# ArduinoInterface_v2.net
KiCad netlist of a schematic drawn in EAGLE
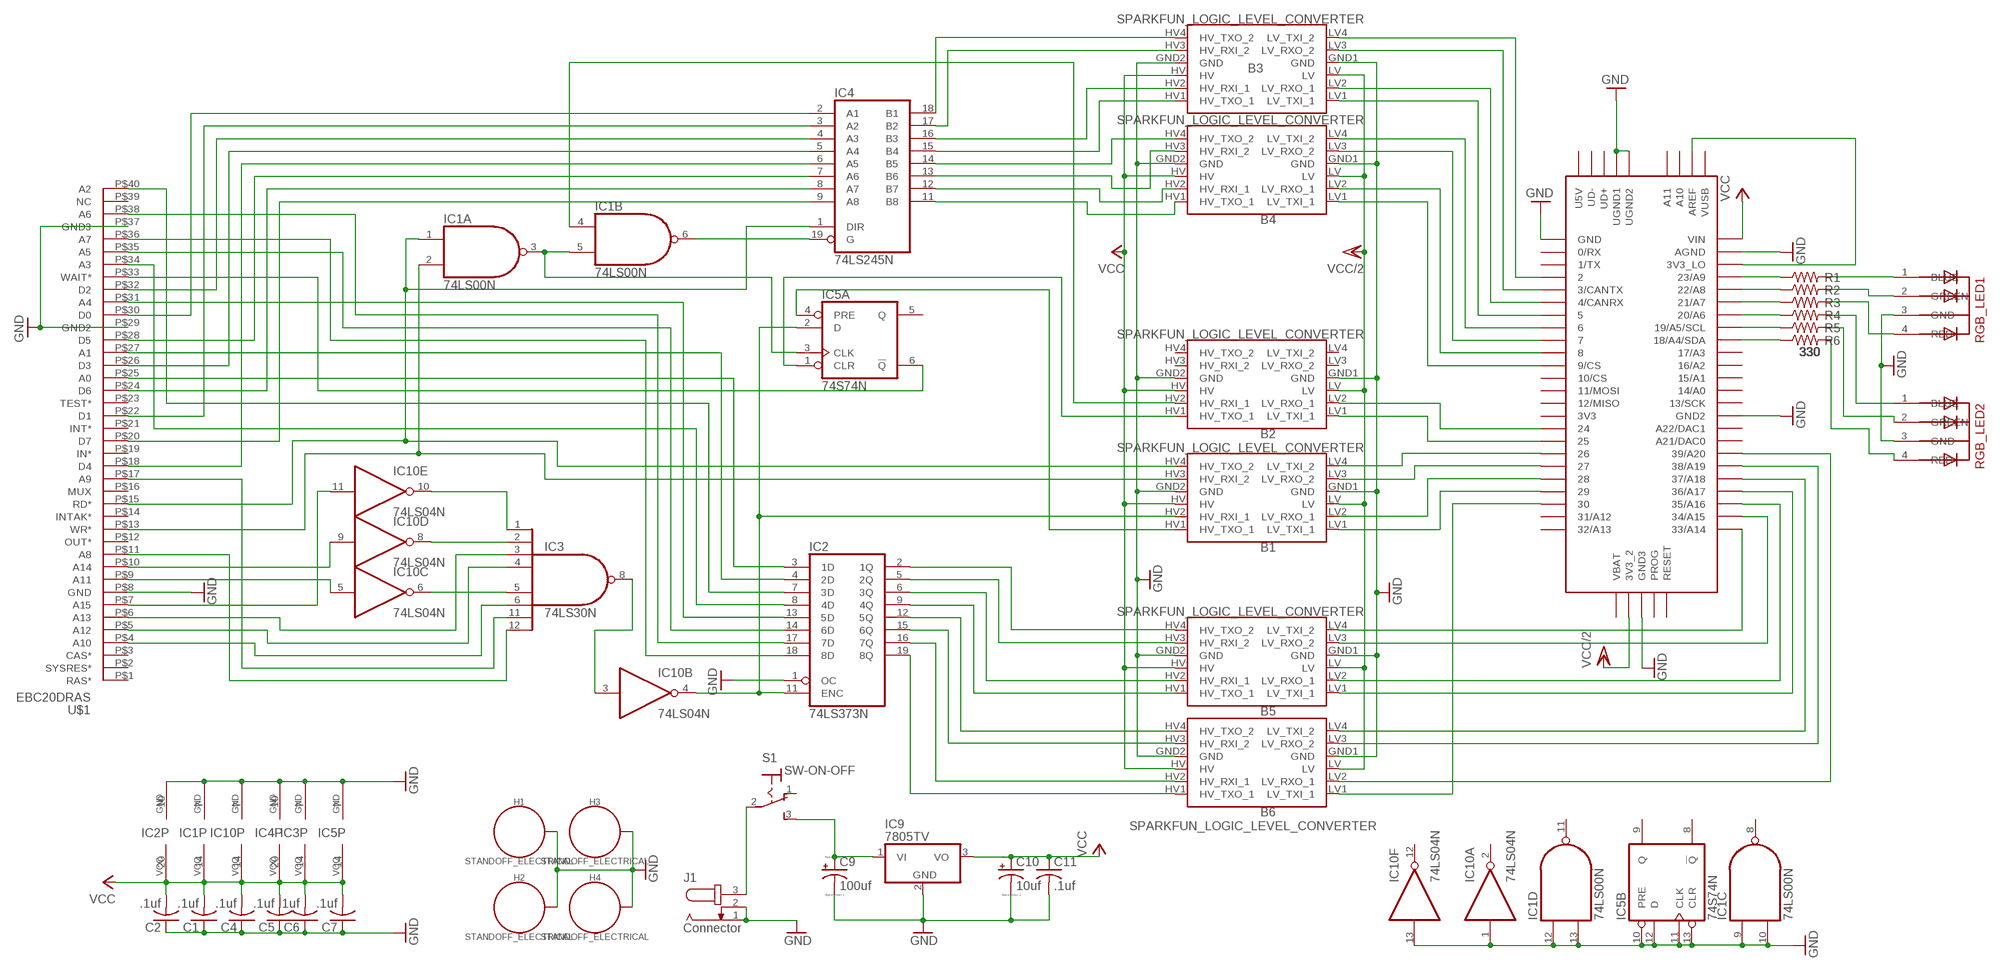
[diagram p0: schematic, sheet 1]

(export (version "E")
  (design (tool "Eeschema 10.0.6"))
  (components
    (comp (ref "B1")
      (value "SPARKFUN_LOGIC_LEVEL_CONVERTER")
      (footprint "eagle-import:SPARKFUN_LOGIC_LEVEL_CONVERTER")
      (libsource (lib "eagle-import") (part "SPARKFUN_LOGIC_LEVEL_CONVERTER"))
    )
    (comp (ref "B2")
      (value "SPARKFUN_LOGIC_LEVEL_CONVERTER")
      (footprint "eagle-import:SPARKFUN_LOGIC_LEVEL_CONVERTER")
      (libsource (lib "eagle-import") (part "SPARKFUN_LOGIC_LEVEL_CONVERTER"))
    )
    (comp (ref "B3")
      (value "SPARKFUN_LOGIC_LEVEL_CONVERTER")
      (footprint "eagle-import:SPARKFUN_LOGIC_LEVEL_CONVERTER")
      (libsource (lib "eagle-import") (part "SPARKFUN_LOGIC_LEVEL_CONVERTER"))
    )
    (comp (ref "B4")
      (value "SPARKFUN_LOGIC_LEVEL_CONVERTER")
      (footprint "eagle-import:SPARKFUN_LOGIC_LEVEL_CONVERTER")
      (libsource (lib "eagle-import") (part "SPARKFUN_LOGIC_LEVEL_CONVERTER"))
    )
    (comp (ref "B5")
      (value "SPARKFUN_LOGIC_LEVEL_CONVERTER")
      (footprint "eagle-import:SPARKFUN_LOGIC_LEVEL_CONVERTER")
      (libsource (lib "eagle-import") (part "SPARKFUN_LOGIC_LEVEL_CONVERTER"))
    )
    (comp (ref "B6")
      (value "SPARKFUN_LOGIC_LEVEL_CONVERTER")
      (footprint "eagle-import:SPARKFUN_LOGIC_LEVEL_CONVERTER")
      (libsource (lib "eagle-import") (part "SPARKFUN_LOGIC_LEVEL_CONVERTER"))
    )
    (comp (ref "C1")
      (value ".1uf")
      (footprint "eagle-import:C025-025X050")
      (libsource (lib "eagle-import") (part "C-US025-025X050"))
    )
    (comp (ref "C2")
      (value ".1uf")
      (footprint "eagle-import:C025-025X050")
      (libsource (lib "eagle-import") (part "C-US025-025X050"))
    )
    (comp (ref "C4")
      (value ".1uf")
      (footprint "eagle-import:C025-025X050")
      (libsource (lib "eagle-import") (part "C-US025-025X050"))
    )
    (comp (ref "C5")
      (value ".1uf")
      (footprint "eagle-import:C025-025X050")
      (libsource (lib "eagle-import") (part "C-US025-025X050"))
    )
    (comp (ref "C6")
      (value ".1uf")
      (footprint "eagle-import:C025-025X050")
      (libsource (lib "eagle-import") (part "C-US025-025X050"))
    )
    (comp (ref "C7")
      (value ".1uf")
      (footprint "eagle-import:C025-025X050")
      (libsource (lib "eagle-import") (part "C-US025-025X050"))
    )
    (comp (ref "C9")
      (value "100uf")
      (footprint "eagle-import:E5-6")
      (libsource (lib "eagle-import") (part "CPOL-USE5-6"))
    )
    (comp (ref "C10")
      (value "10uf")
      (footprint "eagle-import:E5-6")
      (libsource (lib "eagle-import") (part "CPOL-USE5-6"))
    )
    (comp (ref "C11")
      (value ".1uf")
      (footprint "eagle-import:C025-025X050")
      (libsource (lib "eagle-import") (part "C-US025-025X050"))
    )
    (comp (ref "H1")
      (value "STANDOFF_ELECTRICAL")
      (footprint "eagle-import:STANDOFF-ELECTRICAL")
      (libsource (lib "eagle-import") (part "STANDOFF_ELECTRICAL"))
    )
    (comp (ref "H2")
      (value "STANDOFF_ELECTRICAL")
      (footprint "eagle-import:STANDOFF-ELECTRICAL")
      (libsource (lib "eagle-import") (part "STANDOFF_ELECTRICAL"))
    )
    (comp (ref "H3")
      (value "STANDOFF_ELECTRICAL")
      (footprint "eagle-import:STANDOFF-ELECTRICAL")
      (libsource (lib "eagle-import") (part "STANDOFF_ELECTRICAL"))
    )
    (comp (ref "H4")
      (value "STANDOFF_ELECTRICAL")
      (footprint "eagle-import:STANDOFF-ELECTRICAL")
      (libsource (lib "eagle-import") (part "STANDOFF_ELECTRICAL"))
    )
    (comp (ref "IC1")
      (value "74LS00N")
      (footprint "eagle-import:DIL14")
      (libsource (lib "eagle-import") (part "7400NLS"))
    )
    (comp (ref "IC2")
      (value "74LS373N")
      (footprint "eagle-import:DIL20")
      (libsource (lib "eagle-import") (part "74373NLS"))
    )
    (comp (ref "IC3")
      (value "74LS30N")
      (footprint "eagle-import:DIL14")
      (libsource (lib "eagle-import") (part "7430NLS"))
    )
    (comp (ref "IC4")
      (value "74LS245N")
      (footprint "eagle-import:DIL20")
      (libsource (lib "eagle-import") (part "74245NLS"))
    )
    (comp (ref "IC5")
      (value "74S74N")
      (footprint "eagle-import:DIL14")
      (libsource (lib "eagle-import") (part "7474NS"))
    )
    (comp (ref "IC9")
      (value "7805TV")
      (footprint "eagle-import:TO220V")
      (libsource (lib "eagle-import") (part "78TV05"))
    )
    (comp (ref "IC10")
      (value "74LS04N")
      (footprint "eagle-import:DIL14")
      (libsource (lib "eagle-import") (part "7404NLS"))
    )
    (comp (ref "J1")
      (value "Connector")
      (footprint "eagle-import:SPC4077")
      (libsource (lib "eagle-import") (part "JACK-PLUG0"))
    )
    (comp (ref "R1")
      (value "330")
      (footprint "eagle-import:0204V")
      (libsource (lib "eagle-import") (part "R-US_0204/2V"))
    )
    (comp (ref "R2")
      (value "330")
      (footprint "eagle-import:0204V")
      (libsource (lib "eagle-import") (part "R-US_0204/2V"))
    )
    (comp (ref "R3")
      (value "330")
      (footprint "eagle-import:0204V")
      (libsource (lib "eagle-import") (part "R-US_0204/2V"))
    )
    (comp (ref "R4")
      (value "330")
      (footprint "eagle-import:0204V")
      (libsource (lib "eagle-import") (part "R-US_0204/2V"))
    )
    (comp (ref "R5")
      (value "330")
      (footprint "eagle-import:0204V")
      (libsource (lib "eagle-import") (part "R-US_0204/2V"))
    )
    (comp (ref "R6")
      (value "330")
      (footprint "eagle-import:0204V")
      (libsource (lib "eagle-import") (part "R-US_0204/2V"))
    )
    (comp (ref "RGB_LED1")
      (value "5MMRGBLED")
      (footprint "eagle-import:LED5MMRGB")
      (libsource (lib "eagle-import") (part "5MMRGBLED"))
    )
    (comp (ref "RGB_LED2")
      (value "5MMRGBLED")
      (footprint "eagle-import:LED5MMRGB")
      (libsource (lib "eagle-import") (part "5MMRGBLED"))
    )
    (comp (ref "S1")
      (value "SW-ON-OFF")
      (footprint "eagle-import:M9040P")
      (libsource (lib "eagle-import") (part "M9040P"))
    )
    (comp (ref "U$1")
      (value "EBC20DRAS")
      (footprint "eagle-import:EBC20DRAS")
      (libsource (lib "eagle-import") (part "EBC20DRAS"))
    )
    (comp (ref "U$2")
      (value "TEENSY_3.5/3.6")
      (footprint "eagle-import:TEENSY_3.5_3.6")
      (libsource (lib "eagle-import") (part "TEENSY_3.5/3.6"))
    )
  )
  (nets
    (net (code "1") (name "GND") (class "Default")
      (node (ref "B1") (pin "GND1") (pinfunction "GND_GND1") (pintype "power_in"))
      (node (ref "B1") (pin "GND2") (pinfunction "GND_GND2") (pintype "power_in"))
      (node (ref "B2") (pin "GND1") (pinfunction "GND_GND1") (pintype "power_in"))
      (node (ref "B2") (pin "GND2") (pinfunction "GND_GND2") (pintype "power_in"))
      (node (ref "B3") (pin "GND1") (pinfunction "GND_GND1") (pintype "power_in"))
      (node (ref "B3") (pin "GND2") (pinfunction "GND_GND2") (pintype "power_in"))
      (node (ref "B4") (pin "GND1") (pinfunction "GND_GND1") (pintype "power_in"))
      (node (ref "B4") (pin "GND2") (pinfunction "GND_GND2") (pintype "power_in"))
      (node (ref "B5") (pin "GND1") (pinfunction "GND_GND1") (pintype "power_in"))
      (node (ref "B5") (pin "GND2") (pinfunction "GND_GND2") (pintype "power_in"))
      (node (ref "B6") (pin "GND1") (pinfunction "GND_GND1") (pintype "power_in"))
      (node (ref "B6") (pin "GND2") (pinfunction "GND_GND2") (pintype "power_in"))
      (node (ref "C1") (pin "1") (pinfunction "1_1") (pintype "passive"))
      (node (ref "C10") (pin "-") (pinfunction "-_-") (pintype "passive"))
      (node (ref "C11") (pin "2") (pinfunction "2_2") (pintype "passive"))
      (node (ref "C2") (pin "1") (pinfunction "1_1") (pintype "passive"))
      (node (ref "C4") (pin "1") (pinfunction "1_1") (pintype "passive"))
      (node (ref "C5") (pin "1") (pinfunction "1_1") (pintype "passive"))
      (node (ref "C6") (pin "1") (pinfunction "1_1") (pintype "passive"))
      (node (ref "C7") (pin "1") (pinfunction "1_1") (pintype "passive"))
      (node (ref "C9") (pin "-") (pinfunction "-_-") (pintype "passive"))
      (node (ref "H1") (pin "P1") (pinfunction "P$1_P1") (pintype "bidirectional"))
      (node (ref "H2") (pin "P1") (pinfunction "P$1_P1") (pintype "bidirectional"))
      (node (ref "H3") (pin "P1") (pinfunction "P$1_P1") (pintype "bidirectional"))
      (node (ref "H4") (pin "P1") (pinfunction "P$1_P1") (pintype "bidirectional"))
      (node (ref "IC1") (pin "10") (pinfunction "I1_10") (pintype "input"))
      (node (ref "IC1") (pin "12") (pinfunction "I0_12") (pintype "input"))
      (node (ref "IC1") (pin "13") (pinfunction "I1_13") (pintype "input"))
      (node (ref "IC1") (pin "7") (pinfunction "GND_7") (pintype "power_in"))
      (node (ref "IC1") (pin "9") (pinfunction "I0_9") (pintype "input"))
      (node (ref "IC10") (pin "1") (pinfunction "I_1") (pintype "input"))
      (node (ref "IC10") (pin "13") (pinfunction "I_13") (pintype "input"))
      (node (ref "IC10") (pin "7") (pinfunction "GND_7") (pintype "power_in"))
      (node (ref "IC2") (pin "1") (pinfunction "OC_1") (pintype "input"))
      (node (ref "IC2") (pin "10") (pinfunction "GND_10") (pintype "power_in"))
      (node (ref "IC3") (pin "7") (pinfunction "GND_7") (pintype "power_in"))
      (node (ref "IC4") (pin "10") (pinfunction "GND_10") (pintype "power_in"))
      (node (ref "IC5") (pin "10") (pinfunction "PRE_10") (pintype "input"))
      (node (ref "IC5") (pin "11") (pinfunction "CLK_11") (pintype "input"))
      (node (ref "IC5") (pin "12") (pinfunction "D_12") (pintype "input"))
      (node (ref "IC5") (pin "13") (pinfunction "CLR_13") (pintype "input"))
      (node (ref "IC5") (pin "7") (pinfunction "GND_7") (pintype "power_in"))
      (node (ref "IC9") (pin "2") (pinfunction "GND_2") (pintype "passive"))
      (node (ref "J1") (pin "1") (pinfunction "1_1") (pintype "passive"))
      (node (ref "J1") (pin "2") (pinfunction "2_2") (pintype "passive"))
      (node (ref "RGB_LED1") (pin "3") (pinfunction "GND_3") (pintype "bidirectional"))
      (node (ref "RGB_LED2") (pin "3") (pinfunction "GND_3") (pintype "bidirectional"))
      (node (ref "U$1") (pin "P$29") (pinfunction "GND2_P$29") (pintype "bidirectional"))
      (node (ref "U$1") (pin "P$37") (pinfunction "GND3_P$37") (pintype "bidirectional"))
      (node (ref "U$1") (pin "P$8") (pinfunction "GND_P$8") (pintype "bidirectional"))
      (node (ref "U$2") (pin "AGND") (pinfunction "AGND_AGND") (pintype "bidirectional"))
      (node (ref "U$2") (pin "GND") (pinfunction "GND_GND") (pintype "bidirectional"))
      (node (ref "U$2") (pin "GND2") (pinfunction "GND2_GND2") (pintype "bidirectional"))
      (node (ref "U$2") (pin "GND3") (pinfunction "GND3_GND3") (pintype "bidirectional"))
      (node (ref "U$2") (pin "UGND1") (pinfunction "UGND1_UGND1") (pintype "bidirectional"))
      (node (ref "U$2") (pin "UGND2") (pinfunction "UGND2_UGND2") (pintype "bidirectional"))
    )
    (net (code "2") (name "Net-(B1-HV_RXI_1)") (class "Default")
      (node (ref "B1") (pin "HV2") (pinfunction "HV_RXI_1_HV2") (pintype "bidirectional"))
      (node (ref "IC10") (pin "4") (pinfunction "O_4") (pintype "output"))
      (node (ref "IC2") (pin "11") (pinfunction "ENC_11") (pintype "input"))
      (node (ref "IC5") (pin "2") (pinfunction "D_2") (pintype "input"))
    )
    (net (code "3") (name "Net-(B1-HV_RXI_2)") (class "Default")
      (node (ref "B1") (pin "HV3") (pinfunction "HV_RXI_2_HV3") (pintype "bidirectional"))
      (node (ref "IC1") (pin "2") (pinfunction "I1_2") (pintype "input"))
      (node (ref "U$1") (pin "P$13") (pinfunction "WR*_P$13") (pintype "bidirectional"))
    )
    (net (code "4") (name "Net-(B1-HV_TXO_1)") (class "Default")
      (node (ref "B1") (pin "HV1") (pinfunction "HV_TXO_1_HV1") (pintype "bidirectional"))
      (node (ref "IC5") (pin "4") (pinfunction "PRE_4") (pintype "input"))
    )
    (net (code "5") (name "Net-(B1-HV_TXO_2)") (class "Default")
      (node (ref "B1") (pin "HV4") (pinfunction "HV_TXO_2_HV4") (pintype "bidirectional"))
      (node (ref "IC1") (pin "1") (pinfunction "I0_1") (pintype "input"))
      (node (ref "IC4") (pin "1") (pinfunction "DIR_1") (pintype "input"))
      (node (ref "U$1") (pin "P$15") (pinfunction "RD*_P$15") (pintype "bidirectional"))
    )
    (net (code "6") (name "Net-(B1-LV_RXO_1)") (class "Default")
      (node (ref "B1") (pin "LV2") (pinfunction "LV_RXO_1_LV2") (pintype "bidirectional"))
      (node (ref "U$2") (pin "28") (pinfunction "28_28") (pintype "bidirectional"))
    )
    (net (code "7") (name "Net-(B1-LV_RXO_2)") (class "Default")
      (node (ref "B1") (pin "LV3") (pinfunction "LV_RXO_2_LV3") (pintype "bidirectional"))
      (node (ref "U$2") (pin "27") (pinfunction "27_27") (pintype "bidirectional"))
    )
    (net (code "8") (name "Net-(B1-LV_TXI_1)") (class "Default")
      (node (ref "B1") (pin "LV1") (pinfunction "LV_TXI_1_LV1") (pintype "bidirectional"))
      (node (ref "U$2") (pin "29") (pinfunction "29_29") (pintype "bidirectional"))
    )
    (net (code "9") (name "Net-(B1-LV_TXI_2)") (class "Default")
      (node (ref "B1") (pin "LV4") (pinfunction "LV_TXI_2_LV4") (pintype "bidirectional"))
      (node (ref "U$2") (pin "26") (pinfunction "26_26") (pintype "bidirectional"))
    )
    (net (code "10") (name "Net-(B2-HV_RXI_1)") (class "Default")
      (node (ref "B2") (pin "HV2") (pinfunction "HV_RXI_1_HV2") (pintype "bidirectional"))
      (node (ref "IC1") (pin "4") (pinfunction "I0_4") (pintype "input"))
    )
    (net (code "11") (name "Net-(B2-HV_TXO_1)") (class "Default")
      (node (ref "B2") (pin "HV1") (pinfunction "HV_TXO_1_HV1") (pintype "bidirectional"))
      (node (ref "IC5") (pin "1") (pinfunction "CLR_1") (pintype "input"))
    )
    (net (code "12") (name "Net-(B2-LV_RXO_1)") (class "Default")
      (node (ref "B2") (pin "LV2") (pinfunction "LV_RXO_1_LV2") (pintype "bidirectional"))
      (node (ref "U$2") (pin "24") (pinfunction "24_24") (pintype "bidirectional"))
    )
    (net (code "13") (name "Net-(B2-LV_TXI_1)") (class "Default")
      (node (ref "B2") (pin "LV1") (pinfunction "LV_TXI_1_LV1") (pintype "bidirectional"))
      (node (ref "U$2") (pin "25") (pinfunction "25_25") (pintype "bidirectional"))
    )
    (net (code "14") (name "Net-(B3-HV_RXI_1)") (class "Default")
      (node (ref "B3") (pin "HV2") (pinfunction "HV_RXI_1_HV2") (pintype "bidirectional"))
      (node (ref "IC4") (pin "16") (pinfunction "B3_16") (pintype "bidirectional"))
    )
    (net (code "15") (name "Net-(B3-HV_RXI_2)") (class "Default")
      (node (ref "B3") (pin "HV3") (pinfunction "HV_RXI_2_HV3") (pintype "bidirectional"))
      (node (ref "IC4") (pin "17") (pinfunction "B2_17") (pintype "bidirectional"))
    )
    (net (code "16") (name "Net-(B3-HV_TXO_1)") (class "Default")
      (node (ref "B3") (pin "HV1") (pinfunction "HV_TXO_1_HV1") (pintype "bidirectional"))
      (node (ref "IC4") (pin "15") (pinfunction "B4_15") (pintype "bidirectional"))
    )
    (net (code "17") (name "Net-(B3-HV_TXO_2)") (class "Default")
      (node (ref "B3") (pin "HV4") (pinfunction "HV_TXO_2_HV4") (pintype "bidirectional"))
      (node (ref "IC4") (pin "18") (pinfunction "B1_18") (pintype "bidirectional"))
    )
    (net (code "18") (name "Net-(B3-LV_RXO_1)") (class "Default")
      (node (ref "B3") (pin "LV2") (pinfunction "LV_RXO_1_LV2") (pintype "bidirectional"))
      (node (ref "U$2") (pin "4/CANRX") (pinfunction "4/CANRX_4/CANRX") (pintype "bidirectional"))
    )
    (net (code "19") (name "Net-(B3-LV_RXO_2)") (class "Default")
      (node (ref "B3") (pin "LV3") (pinfunction "LV_RXO_2_LV3") (pintype "bidirectional"))
      (node (ref "U$2") (pin "3/CANTX") (pinfunction "3/CANTX_3/CANTX") (pintype "bidirectional"))
    )
    (net (code "20") (name "Net-(B3-LV_TXI_1)") (class "Default")
      (node (ref "B3") (pin "LV1") (pinfunction "LV_TXI_1_LV1") (pintype "bidirectional"))
      (node (ref "U$2") (pin "5") (pinfunction "5_5") (pintype "bidirectional"))
    )
    (net (code "21") (name "Net-(B3-LV_TXI_2)") (class "Default")
      (node (ref "B3") (pin "LV4") (pinfunction "LV_TXI_2_LV4") (pintype "bidirectional"))
      (node (ref "U$2") (pin "2") (pinfunction "2_2") (pintype "bidirectional"))
    )
    (net (code "22") (name "Net-(B4-HV_RXI_1)") (class "Default")
      (node (ref "B4") (pin "HV2") (pinfunction "HV_RXI_1_HV2") (pintype "bidirectional"))
      (node (ref "IC4") (pin "12") (pinfunction "B7_12") (pintype "bidirectional"))
    )
    (net (code "23") (name "Net-(B4-HV_RXI_2)") (class "Default")
      (node (ref "B4") (pin "HV3") (pinfunction "HV_RXI_2_HV3") (pintype "bidirectional"))
      (node (ref "IC4") (pin "13") (pinfunction "B6_13") (pintype "bidirectional"))
    )
    (net (code "24") (name "Net-(B4-HV_TXO_1)") (class "Default")
      (node (ref "B4") (pin "HV1") (pinfunction "HV_TXO_1_HV1") (pintype "bidirectional"))
      (node (ref "IC4") (pin "11") (pinfunction "B8_11") (pintype "bidirectional"))
    )
    (net (code "25") (name "Net-(B4-HV_TXO_2)") (class "Default")
      (node (ref "B4") (pin "HV4") (pinfunction "HV_TXO_2_HV4") (pintype "bidirectional"))
      (node (ref "IC4") (pin "14") (pinfunction "B5_14") (pintype "bidirectional"))
    )
    (net (code "26") (name "Net-(B4-LV_RXO_1)") (class "Default")
      (node (ref "B4") (pin "LV2") (pinfunction "LV_RXO_1_LV2") (pintype "bidirectional"))
      (node (ref "U$2") (pin "8") (pinfunction "8_8") (pintype "bidirectional"))
    )
    (net (code "27") (name "Net-(B4-LV_RXO_2)") (class "Default")
      (node (ref "B4") (pin "LV3") (pinfunction "LV_RXO_2_LV3") (pintype "bidirectional"))
      (node (ref "U$2") (pin "7") (pinfunction "7_7") (pintype "bidirectional"))
    )
    (net (code "28") (name "Net-(B4-LV_TXI_1)") (class "Default")
      (node (ref "B4") (pin "LV1") (pinfunction "LV_TXI_1_LV1") (pintype "bidirectional"))
      (node (ref "U$2") (pin "9/CS") (pinfunction "9/CS_9/CS") (pintype "bidirectional"))
    )
    (net (code "29") (name "Net-(B4-LV_TXI_2)") (class "Default")
      (node (ref "B4") (pin "LV4") (pinfunction "LV_TXI_2_LV4") (pintype "bidirectional"))
      (node (ref "U$2") (pin "6") (pinfunction "6_6") (pintype "bidirectional"))
    )
    (net (code "30") (name "Net-(B5-HV_RXI_1)") (class "Default")
      (node (ref "B5") (pin "HV2") (pinfunction "HV_RXI_1_HV2") (pintype "bidirectional"))
      (node (ref "IC2") (pin "6") (pinfunction "3Q_6") (pintype "tri_state"))
    )
    (net (code "31") (name "Net-(B5-HV_RXI_2)") (class "Default")
      (node (ref "B5") (pin "HV3") (pinfunction "HV_RXI_2_HV3") (pintype "bidirectional"))
      (node (ref "IC2") (pin "5") (pinfunction "2Q_5") (pintype "tri_state"))
    )
    (net (code "32") (name "Net-(B5-HV_TXO_1)") (class "Default")
      (node (ref "B5") (pin "HV1") (pinfunction "HV_TXO_1_HV1") (pintype "bidirectional"))
      (node (ref "IC2") (pin "9") (pinfunction "4Q_9") (pintype "tri_state"))
    )
    (net (code "33") (name "Net-(B5-HV_TXO_2)") (class "Default")
      (node (ref "B5") (pin "HV4") (pinfunction "HV_TXO_2_HV4") (pintype "bidirectional"))
      (node (ref "IC2") (pin "2") (pinfunction "1Q_2") (pintype "tri_state"))
    )
    (net (code "34") (name "Net-(B5-LV_RXO_1)") (class "Default")
      (node (ref "B5") (pin "LV2") (pinfunction "LV_RXO_1_LV2") (pintype "bidirectional"))
      (node (ref "U$2") (pin "35/A16") (pinfunction "35/A16_35/A16") (pintype "bidirectional"))
    )
    (net (code "35") (name "Net-(B5-LV_RXO_2)") (class "Default")
      (node (ref "B5") (pin "LV3") (pinfunction "LV_RXO_2_LV3") (pintype "bidirectional"))
      (node (ref "U$2") (pin "34/A15") (pinfunction "34/A15_34/A15") (pintype "bidirectional"))
    )
    (net (code "36") (name "Net-(B5-LV_TXI_1)") (class "Default")
      (node (ref "B5") (pin "LV1") (pinfunction "LV_TXI_1_LV1") (pintype "bidirectional"))
      (node (ref "U$2") (pin "36/A17") (pinfunction "36/A17_36/A17") (pintype "bidirectional"))
    )
    (net (code "37") (name "Net-(B5-LV_TXI_2)") (class "Default")
      (node (ref "B5") (pin "LV4") (pinfunction "LV_TXI_2_LV4") (pintype "bidirectional"))
      (node (ref "U$2") (pin "33/A14") (pinfunction "33/A14_33/A14") (pintype "bidirectional"))
    )
    (net (code "38") (name "Net-(B6-HV_RXI_1)") (class "Default")
      (node (ref "B6") (pin "HV2") (pinfunction "HV_RXI_1_HV2") (pintype "bidirectional"))
      (node (ref "IC2") (pin "16") (pinfunction "7Q_16") (pintype "tri_state"))
    )
    (net (code "39") (name "Net-(B6-HV_RXI_2)") (class "Default")
      (node (ref "B6") (pin "HV3") (pinfunction "HV_RXI_2_HV3") (pintype "bidirectional"))
      (node (ref "IC2") (pin "15") (pinfunction "6Q_15") (pintype "tri_state"))
    )
    (net (code "40") (name "Net-(B6-HV_TXO_1)") (class "Default")
      (node (ref "B6") (pin "HV1") (pinfunction "HV_TXO_1_HV1") (pintype "bidirectional"))
      (node (ref "IC2") (pin "19") (pinfunction "8Q_19") (pintype "tri_state"))
    )
    (net (code "41") (name "Net-(B6-HV_TXO_2)") (class "Default")
      (node (ref "B6") (pin "HV4") (pinfunction "HV_TXO_2_HV4") (pintype "bidirectional"))
      (node (ref "IC2") (pin "12") (pinfunction "5Q_12") (pintype "tri_state"))
    )
    (net (code "42") (name "Net-(B6-LV_RXO_1)") (class "Default")
      (node (ref "B6") (pin "LV2") (pinfunction "LV_RXO_1_LV2") (pintype "bidirectional"))
      (node (ref "U$2") (pin "39/A20") (pinfunction "39/A20_39/A20") (pintype "bidirectional"))
    )
    (net (code "43") (name "Net-(B6-LV_RXO_2)") (class "Default")
      (node (ref "B6") (pin "LV3") (pinfunction "LV_RXO_2_LV3") (pintype "bidirectional"))
      (node (ref "U$2") (pin "38/A19") (pinfunction "38/A19_38/A19") (pintype "bidirectional"))
    )
    (net (code "44") (name "Net-(B6-LV_TXI_1)") (class "Default")
      (node (ref "B6") (pin "LV1") (pinfunction "LV_TXI_1_LV1") (pintype "bidirectional"))
      (node (ref "U$2") (pin "30") (pinfunction "30_30") (pintype "bidirectional"))
    )
    (net (code "45") (name "Net-(B6-LV_TXI_2)") (class "Default")
      (node (ref "B6") (pin "LV4") (pinfunction "LV_TXI_2_LV4") (pintype "bidirectional"))
      (node (ref "U$2") (pin "37/A18") (pinfunction "37/A18_37/A18") (pintype "bidirectional"))
    )
    (net (code "46") (name "Net-(IC1A-O)") (class "Default")
      (node (ref "IC1") (pin "3") (pinfunction "O_3") (pintype "output"))
      (node (ref "IC1") (pin "5") (pinfunction "I1_5") (pintype "input"))
      (node (ref "IC5") (pin "3") (pinfunction "CLK_3") (pintype "input"))
    )
    (net (code "47") (name "Net-(IC1B-O)") (class "Default")
      (node (ref "IC1") (pin "6") (pinfunction "O_6") (pintype "output"))
      (node (ref "IC4") (pin "19") (pinfunction "G_19") (pintype "input"))
    )
    (net (code "48") (name "Net-(IC2A-1D)") (class "Default")
      (node (ref "IC2") (pin "3") (pinfunction "1D_3") (pintype "input"))
      (node (ref "U$1") (pin "P$25") (pinfunction "A0_P$25") (pintype "bidirectional"))
    )
    (net (code "49") (name "Net-(IC2A-2D)") (class "Default")
      (node (ref "IC2") (pin "4") (pinfunction "2D_4") (pintype "input"))
      (node (ref "U$1") (pin "P$27") (pinfunction "A1_P$27") (pintype "bidirectional"))
    )
    (net (code "50") (name "Net-(IC2A-3D)") (class "Default")
      (node (ref "IC2") (pin "7") (pinfunction "3D_7") (pintype "input"))
      (node (ref "U$1") (pin "P$40") (pinfunction "A2_P$40") (pintype "bidirectional"))
    )
    (net (code "51") (name "Net-(IC2A-4D)") (class "Default")
      (node (ref "IC2") (pin "8") (pinfunction "4D_8") (pintype "input"))
      (node (ref "U$1") (pin "P$34") (pinfunction "A3_P$34") (pintype "bidirectional"))
    )
    (net (code "52") (name "Net-(IC2A-5D)") (class "Default")
      (node (ref "IC2") (pin "13") (pinfunction "5D_13") (pintype "input"))
      (node (ref "U$1") (pin "P$31") (pinfunction "A4_P$31") (pintype "bidirectional"))
    )
    (net (code "53") (name "Net-(IC2A-6D)") (class "Default")
      (node (ref "IC2") (pin "14") (pinfunction "6D_14") (pintype "input"))
      (node (ref "U$1") (pin "P$35") (pinfunction "A5_P$35") (pintype "bidirectional"))
    )
    (net (code "54") (name "Net-(IC2A-7D)") (class "Default")
      (node (ref "IC2") (pin "17") (pinfunction "7D_17") (pintype "input"))
      (node (ref "U$1") (pin "P$38") (pinfunction "A6_P$38") (pintype "bidirectional"))
    )
    (net (code "55") (name "Net-(IC2A-8D)") (class "Default")
      (node (ref "IC2") (pin "18") (pinfunction "8D_18") (pintype "input"))
      (node (ref "U$1") (pin "P$36") (pinfunction "A7_P$36") (pintype "bidirectional"))
    )
    (net (code "56") (name "Net-(IC3A-I2)") (class "Default")
      (node (ref "IC3") (pin "3") (pinfunction "I2_3") (pintype "input"))
      (node (ref "U$1") (pin "P$6") (pinfunction "A13_P$6") (pintype "bidirectional"))
    )
    (net (code "57") (name "Net-(IC3A-I3)") (class "Default")
      (node (ref "IC3") (pin "4") (pinfunction "I3_4") (pintype "input"))
      (node (ref "U$1") (pin "P$5") (pinfunction "A12_P$5") (pintype "bidirectional"))
    )
    (net (code "58") (name "Net-(IC3A-I5)") (class "Default")
      (node (ref "IC3") (pin "6") (pinfunction "I5_6") (pintype "input"))
      (node (ref "U$1") (pin "P$4") (pinfunction "A10_P$4") (pintype "bidirectional"))
    )
    (net (code "59") (name "Net-(IC3A-I6)") (class "Default")
      (node (ref "IC3") (pin "11") (pinfunction "I6_11") (pintype "input"))
      (node (ref "U$1") (pin "P$17") (pinfunction "A9_P$17") (pintype "bidirectional"))
    )
    (net (code "60") (name "Net-(IC3A-I7)") (class "Default")
      (node (ref "IC3") (pin "12") (pinfunction "I7_12") (pintype "input"))
      (node (ref "U$1") (pin "P$11") (pinfunction "A8_P$11") (pintype "bidirectional"))
    )
    (net (code "61") (name "Net-(IC4A-A1)") (class "Default")
      (node (ref "IC4") (pin "2") (pinfunction "A1_2") (pintype "bidirectional"))
      (node (ref "U$1") (pin "P$30") (pinfunction "D0_P$30") (pintype "bidirectional"))
    )
    (net (code "62") (name "Net-(IC4A-A2)") (class "Default")
      (node (ref "IC4") (pin "3") (pinfunction "A2_3") (pintype "bidirectional"))
      (node (ref "U$1") (pin "P$22") (pinfunction "D1_P$22") (pintype "bidirectional"))
    )
    (net (code "63") (name "Net-(IC4A-A3)") (class "Default")
      (node (ref "IC4") (pin "4") (pinfunction "A3_4") (pintype "bidirectional"))
      (node (ref "U$1") (pin "P$32") (pinfunction "D2_P$32") (pintype "bidirectional"))
    )
    (net (code "64") (name "Net-(IC4A-A4)") (class "Default")
      (node (ref "IC4") (pin "5") (pinfunction "A4_5") (pintype "bidirectional"))
      (node (ref "U$1") (pin "P$26") (pinfunction "D3_P$26") (pintype "bidirectional"))
    )
    (net (code "65") (name "Net-(IC4A-A5)") (class "Default")
      (node (ref "IC4") (pin "6") (pinfunction "A5_6") (pintype "bidirectional"))
      (node (ref "U$1") (pin "P$18") (pinfunction "D4_P$18") (pintype "bidirectional"))
    )
    (net (code "66") (name "Net-(IC4A-A6)") (class "Default")
      (node (ref "IC4") (pin "7") (pinfunction "A6_7") (pintype "bidirectional"))
      (node (ref "U$1") (pin "P$28") (pinfunction "D5_P$28") (pintype "bidirectional"))
    )
    (net (code "67") (name "Net-(IC4A-A7)") (class "Default")
      (node (ref "IC4") (pin "8") (pinfunction "A7_8") (pintype "bidirectional"))
      (node (ref "U$1") (pin "P$24") (pinfunction "D6_P$24") (pintype "bidirectional"))
    )
    (net (code "68") (name "Net-(IC4A-A8)") (class "Default")
      (node (ref "IC4") (pin "9") (pinfunction "A8_9") (pintype "bidirectional"))
      (node (ref "U$1") (pin "P$20") (pinfunction "D7_P$20") (pintype "bidirectional"))
    )
    (net (code "69") (name "Net-(IC5A-~{Q})") (class "Default")
      (node (ref "IC5") (pin "6") (pinfunction "~{Q}_6") (pintype "output"))
      (node (ref "U$1") (pin "P$33") (pinfunction "WAIT*_P$33") (pintype "bidirectional"))
    )
    (net (code "70") (name "Net-(IC9-VI)") (class "Default")
      (node (ref "C9") (pin "+") (pinfunction "+_+") (pintype "passive"))
      (node (ref "IC9") (pin "1") (pinfunction "VI_1") (pintype "input"))
      (node (ref "S1") (pin "3") (pinfunction "S_3") (pintype "passive"))
    )
    (net (code "71") (name "Net-(IC10B-I)") (class "Default")
      (node (ref "IC10") (pin "3") (pinfunction "I_3") (pintype "input"))
      (node (ref "IC3") (pin "8") (pinfunction "O_8") (pintype "output"))
    )
    (net (code "72") (name "Net-(IC10C-I)") (class "Default")
      (node (ref "IC10") (pin "5") (pinfunction "I_5") (pintype "input"))
      (node (ref "U$1") (pin "P$9") (pinfunction "A11_P$9") (pintype "bidirectional"))
    )
    (net (code "73") (name "Net-(IC10C-O)") (class "Default")
      (node (ref "IC10") (pin "6") (pinfunction "O_6") (pintype "output"))
      (node (ref "IC3") (pin "5") (pinfunction "I4_5") (pintype "input"))
    )
    (net (code "74") (name "Net-(IC10D-I)") (class "Default")
      (node (ref "IC10") (pin "9") (pinfunction "I_9") (pintype "input"))
      (node (ref "U$1") (pin "P$10") (pinfunction "A14_P$10") (pintype "bidirectional"))
    )
    (net (code "75") (name "Net-(IC10D-O)") (class "Default")
      (node (ref "IC10") (pin "8") (pinfunction "O_8") (pintype "output"))
      (node (ref "IC3") (pin "2") (pinfunction "I1_2") (pintype "input"))
    )
    (net (code "76") (name "Net-(IC10E-I)") (class "Default")
      (node (ref "IC10") (pin "11") (pinfunction "I_11") (pintype "input"))
      (node (ref "U$1") (pin "P$7") (pinfunction "A15_P$7") (pintype "bidirectional"))
    )
    (net (code "77") (name "Net-(IC10E-O)") (class "Default")
      (node (ref "IC10") (pin "10") (pinfunction "O_10") (pintype "output"))
      (node (ref "IC3") (pin "1") (pinfunction "I0_1") (pintype "input"))
    )
    (net (code "78") (name "Net-(R1-Pad1)") (class "Default")
      (node (ref "R1") (pin "1") (pinfunction "1_1") (pintype "passive"))
      (node (ref "U$2") (pin "23/A9") (pinfunction "23/A9_23/A9") (pintype "bidirectional"))
    )
    (net (code "79") (name "Net-(R2-Pad1)") (class "Default")
      (node (ref "R2") (pin "1") (pinfunction "1_1") (pintype "passive"))
      (node (ref "U$2") (pin "22/A8") (pinfunction "22/A8_22/A8") (pintype "bidirectional"))
    )
    (net (code "80") (name "Net-(R3-Pad1)") (class "Default")
      (node (ref "R3") (pin "1") (pinfunction "1_1") (pintype "passive"))
      (node (ref "U$2") (pin "21/A7") (pinfunction "21/A7_21/A7") (pintype "bidirectional"))
    )
    (net (code "81") (name "Net-(R4-Pad1)") (class "Default")
      (node (ref "R4") (pin "1") (pinfunction "1_1") (pintype "passive"))
      (node (ref "U$2") (pin "20/A6") (pinfunction "20/A6_20/A6") (pintype "bidirectional"))
    )
    (net (code "82") (name "Net-(R5-Pad1)") (class "Default")
      (node (ref "R5") (pin "1") (pinfunction "1_1") (pintype "passive"))
      (node (ref "U$2") (pin "19/A5/SCL") (pinfunction "19/A5/SCL_19/A5/SCL") (pintype "bidirectional"))
    )
    (net (code "83") (name "Net-(R6-Pad1)") (class "Default")
      (node (ref "R6") (pin "1") (pinfunction "1_1") (pintype "passive"))
      (node (ref "U$2") (pin "18/A4/SDA") (pinfunction "18/A4/SDA_18/A4/SDA") (pintype "bidirectional"))
    )
    (net (code "84") (name "Net-(RGB_LED1-BLUE)") (class "Default")
      (node (ref "R1") (pin "2") (pinfunction "2_2") (pintype "passive"))
      (node (ref "RGB_LED1") (pin "1") (pinfunction "BLUE_1") (pintype "bidirectional"))
    )
    (net (code "85") (name "Net-(RGB_LED1-GREEN)") (class "Default")
      (node (ref "R2") (pin "2") (pinfunction "2_2") (pintype "passive"))
      (node (ref "RGB_LED1") (pin "2") (pinfunction "GREEN_2") (pintype "bidirectional"))
    )
    (net (code "86") (name "Net-(RGB_LED1-RED)") (class "Default")
      (node (ref "R3") (pin "2") (pinfunction "2_2") (pintype "passive"))
      (node (ref "RGB_LED1") (pin "4") (pinfunction "RED_4") (pintype "bidirectional"))
    )
    (net (code "87") (name "Net-(RGB_LED2-BLUE)") (class "Default")
      (node (ref "R4") (pin "2") (pinfunction "2_2") (pintype "passive"))
      (node (ref "RGB_LED2") (pin "1") (pinfunction "BLUE_1") (pintype "bidirectional"))
    )
    (net (code "88") (name "Net-(RGB_LED2-GREEN)") (class "Default")
      (node (ref "R5") (pin "2") (pinfunction "2_2") (pintype "passive"))
      (node (ref "RGB_LED2") (pin "2") (pinfunction "GREEN_2") (pintype "bidirectional"))
    )
    (net (code "89") (name "Net-(RGB_LED2-RED)") (class "Default")
      (node (ref "R6") (pin "2") (pinfunction "2_2") (pintype "passive"))
      (node (ref "RGB_LED2") (pin "4") (pinfunction "RED_4") (pintype "bidirectional"))
    )
    (net (code "90") (name "Net-(S1-P)") (class "Default")
      (node (ref "J1") (pin "3") (pinfunction "3_3") (pintype "passive"))
      (node (ref "S1") (pin "2") (pinfunction "P_2") (pintype "passive"))
    )
    (net (code "91") (name "Net-(U$2-Pad3V3_LO)") (class "Default")
      (node (ref "U$2") (pin "3V3_LO") (pinfunction "3V3_LO_3V3_LO") (pintype "bidirectional"))
      (node (ref "U$2") (pin "AREF") (pinfunction "AREF_AREF") (pintype "bidirectional"))
    )
    (net (code "92") (name "VCC") (class "Default")
      (node (ref "B1") (pin "HV") (pinfunction "HV_HV") (pintype "power_in"))
      (node (ref "B2") (pin "HV") (pinfunction "HV_HV") (pintype "power_in"))
      (node (ref "B3") (pin "HV") (pinfunction "HV_HV") (pintype "power_in"))
      (node (ref "B4") (pin "HV") (pinfunction "HV_HV") (pintype "power_in"))
      (node (ref "B5") (pin "HV") (pinfunction "HV_HV") (pintype "power_in"))
      (node (ref "B6") (pin "HV") (pinfunction "HV_HV") (pintype "power_in"))
      (node (ref "C1") (pin "2") (pinfunction "2_2") (pintype "passive"))
      (node (ref "C10") (pin "+") (pinfunction "+_+") (pintype "passive"))
      (node (ref "C11") (pin "1") (pinfunction "1_1") (pintype "passive"))
      (node (ref "C2") (pin "2") (pinfunction "2_2") (pintype "passive"))
      (node (ref "C4") (pin "2") (pinfunction "2_2") (pintype "passive"))
      (node (ref "C5") (pin "2") (pinfunction "2_2") (pintype "passive"))
      (node (ref "C6") (pin "2") (pinfunction "2_2") (pintype "passive"))
      (node (ref "C7") (pin "2") (pinfunction "2_2") (pintype "passive"))
      (node (ref "IC1") (pin "14") (pinfunction "VCC_14") (pintype "power_in"))
      (node (ref "IC10") (pin "14") (pinfunction "VCC_14") (pintype "power_in"))
      (node (ref "IC2") (pin "20") (pinfunction "VCC_20") (pintype "power_in"))
      (node (ref "IC3") (pin "14") (pinfunction "VCC_14") (pintype "power_in"))
      (node (ref "IC4") (pin "20") (pinfunction "VCC_20") (pintype "power_in"))
      (node (ref "IC5") (pin "14") (pinfunction "VCC_14") (pintype "power_in"))
      (node (ref "IC9") (pin "3") (pinfunction "VO_3") (pintype "passive"))
      (node (ref "U$2") (pin "VIN") (pinfunction "VIN_VIN") (pintype "bidirectional"))
    )
    (net (code "93") (name "VCC{slash}2") (class "Default")
      (node (ref "B1") (pin "LV") (pinfunction "LV_LV") (pintype "power_in"))
      (node (ref "B2") (pin "LV") (pinfunction "LV_LV") (pintype "power_in"))
      (node (ref "B3") (pin "LV") (pinfunction "LV_LV") (pintype "power_in"))
      (node (ref "B4") (pin "LV") (pinfunction "LV_LV") (pintype "power_in"))
      (node (ref "B5") (pin "LV") (pinfunction "LV_LV") (pintype "power_in"))
      (node (ref "B6") (pin "LV") (pinfunction "LV_LV") (pintype "power_in"))
      (node (ref "U$2") (pin "3V3_2") (pinfunction "3V3_2_3V3_2") (pintype "bidirectional"))
    )
    (net (code "94") (name "unconnected-(B2-HV_RXI_2-PadHV3)") (class "Default")
      (node (ref "B2") (pin "HV3") (pinfunction "HV_RXI_2_HV3") (pintype "bidirectional"))
    )
    (net (code "95") (name "unconnected-(B2-HV_TXO_2-PadHV4)") (class "Default")
      (node (ref "B2") (pin "HV4") (pinfunction "HV_TXO_2_HV4") (pintype "bidirectional"))
    )
    (net (code "96") (name "unconnected-(B2-LV_RXO_2-PadLV3)") (class "Default")
      (node (ref "B2") (pin "LV3") (pinfunction "LV_RXO_2_LV3") (pintype "bidirectional"))
    )
    (net (code "97") (name "unconnected-(B2-LV_TXI_2-PadLV4)") (class "Default")
      (node (ref "B2") (pin "LV4") (pinfunction "LV_TXI_2_LV4") (pintype "bidirectional"))
    )
    (net (code "98") (name "unconnected-(IC1C-O-Pad8)") (class "Default")
      (node (ref "IC1") (pin "8") (pinfunction "O_8") (pintype "output"))
    )
    (net (code "99") (name "unconnected-(IC1D-O-Pad11)") (class "Default")
      (node (ref "IC1") (pin "11") (pinfunction "O_11") (pintype "output"))
    )
    (net (code "100") (name "unconnected-(IC5A-Q-Pad5)") (class "Default")
      (node (ref "IC5") (pin "5") (pinfunction "Q_5") (pintype "output"))
    )
    (net (code "101") (name "unconnected-(IC5B-Q-Pad9)") (class "Default")
      (node (ref "IC5") (pin "9") (pinfunction "Q_9") (pintype "output"))
    )
    (net (code "102") (name "unconnected-(IC5B-~{Q}-Pad8)") (class "Default")
      (node (ref "IC5") (pin "8") (pinfunction "~{Q}_8") (pintype "output"))
    )
    (net (code "103") (name "unconnected-(IC10A-O-Pad2)") (class "Default")
      (node (ref "IC10") (pin "2") (pinfunction "O_2") (pintype "output"))
    )
    (net (code "104") (name "unconnected-(IC10F-O-Pad12)") (class "Default")
      (node (ref "IC10") (pin "12") (pinfunction "O_12") (pintype "output"))
    )
    (net (code "105") (name "unconnected-(S1-O-Pad1)") (class "Default")
      (node (ref "S1") (pin "1") (pinfunction "O_1") (pintype "passive"))
    )
    (net (code "106") (name "unconnected-(U$1-CAS*-PadP$3)") (class "Default")
      (node (ref "U$1") (pin "P$3") (pinfunction "CAS*_P$3") (pintype "bidirectional"))
    )
    (net (code "107") (name "unconnected-(U$1-IN*-PadP$19)") (class "Default")
      (node (ref "U$1") (pin "P$19") (pinfunction "IN*_P$19") (pintype "bidirectional"))
    )
    (net (code "108") (name "unconnected-(U$1-INT*-PadP$21)") (class "Default")
      (node (ref "U$1") (pin "P$21") (pinfunction "INT*_P$21") (pintype "bidirectional"))
    )
    (net (code "109") (name "unconnected-(U$1-INTAK*-PadP$14)") (class "Default")
      (node (ref "U$1") (pin "P$14") (pinfunction "INTAK*_P$14") (pintype "bidirectional"))
    )
    (net (code "110") (name "unconnected-(U$1-MUX-PadP$16)") (class "Default")
      (node (ref "U$1") (pin "P$16") (pinfunction "MUX_P$16") (pintype "bidirectional"))
    )
    (net (code "111") (name "unconnected-(U$1-NC-PadP$39)") (class "Default")
      (node (ref "U$1") (pin "P$39") (pinfunction "NC_P$39") (pintype "bidirectional"))
    )
    (net (code "112") (name "unconnected-(U$1-OUT*-PadP$12)") (class "Default")
      (node (ref "U$1") (pin "P$12") (pinfunction "OUT*_P$12") (pintype "bidirectional"))
    )
    (net (code "113") (name "unconnected-(U$1-RAS*-PadP$1)") (class "Default")
      (node (ref "U$1") (pin "P$1") (pinfunction "RAS*_P$1") (pintype "bidirectional"))
    )
    (net (code "114") (name "unconnected-(U$1-SYSRES*-PadP$2)") (class "Default")
      (node (ref "U$1") (pin "P$2") (pinfunction "SYSRES*_P$2") (pintype "bidirectional"))
    )
    (net (code "115") (name "unconnected-(U$1-TEST*-PadP$23)") (class "Default")
      (node (ref "U$1") (pin "P$23") (pinfunction "TEST*_P$23") (pintype "bidirectional"))
    )
    (net (code "116") (name "unconnected-(U$2-A21{slash}DAC0-Pad21{slash}DAC0)") (class "Default")
      (node (ref "U$2") (pin "21/DAC0") (pinfunction "A21/DAC0_21/DAC0") (pintype "bidirectional"))
    )
    (net (code "117") (name "unconnected-(U$2-Pad0{slash}RX)") (class "Default")
      (node (ref "U$2") (pin "0/RX") (pinfunction "0/RX_0/RX") (pintype "bidirectional"))
    )
    (net (code "118") (name "unconnected-(U$2-Pad1{slash}TX)") (class "Default")
      (node (ref "U$2") (pin "1/TX") (pinfunction "1/TX_1/TX") (pintype "bidirectional"))
    )
    (net (code "119") (name "unconnected-(U$2-Pad3V3)") (class "Default")
      (node (ref "U$2") (pin "3V3") (pinfunction "3V3_3V3") (pintype "bidirectional"))
    )
    (net (code "120") (name "unconnected-(U$2-Pad10{slash}CS)") (class "Default")
      (node (ref "U$2") (pin "10/CS") (pinfunction "10/CS_10/CS") (pintype "bidirectional"))
    )
    (net (code "121") (name "unconnected-(U$2-Pad11{slash}MOSI)") (class "Default")
      (node (ref "U$2") (pin "11/MOSI") (pinfunction "11/MOSI_11/MOSI") (pintype "bidirectional"))
    )
    (net (code "122") (name "unconnected-(U$2-Pad12{slash}MISO)") (class "Default")
      (node (ref "U$2") (pin "12/MISO") (pinfunction "12/MISO_12/MISO") (pintype "bidirectional"))
    )
    (net (code "123") (name "unconnected-(U$2-Pad13{slash}SCK)") (class "Default")
      (node (ref "U$2") (pin "13/SCK") (pinfunction "13/SCK_13/SCK") (pintype "bidirectional"))
    )
    (net (code "124") (name "unconnected-(U$2-Pad14{slash}A0)") (class "Default")
      (node (ref "U$2") (pin "14/A0") (pinfunction "14/A0_14/A0") (pintype "bidirectional"))
    )
    (net (code "125") (name "unconnected-(U$2-Pad15{slash}A1)") (class "Default")
      (node (ref "U$2") (pin "15/A1") (pinfunction "15/A1_15/A1") (pintype "bidirectional"))
    )
    (net (code "126") (name "unconnected-(U$2-Pad16{slash}A2)") (class "Default")
      (node (ref "U$2") (pin "16/A2") (pinfunction "16/A2_16/A2") (pintype "bidirectional"))
    )
    (net (code "127") (name "unconnected-(U$2-Pad17{slash}A3)") (class "Default")
      (node (ref "U$2") (pin "17/A3") (pinfunction "17/A3_17/A3") (pintype "bidirectional"))
    )
    (net (code "128") (name "unconnected-(U$2-Pad31{slash}A12)") (class "Default")
      (node (ref "U$2") (pin "31/A12") (pinfunction "31/A12_31/A12") (pintype "bidirectional"))
    )
    (net (code "129") (name "unconnected-(U$2-Pad32{slash}A13)") (class "Default")
      (node (ref "U$2") (pin "32/A13") (pinfunction "32/A13_32/A13") (pintype "bidirectional"))
    )
    (net (code "130") (name "unconnected-(U$2-PadA10)") (class "Default")
      (node (ref "U$2") (pin "A10") (pinfunction "A10_A10") (pintype "bidirectional"))
    )
    (net (code "131") (name "unconnected-(U$2-PadA11)") (class "Default")
      (node (ref "U$2") (pin "A11") (pinfunction "A11_A11") (pintype "bidirectional"))
    )
    (net (code "132") (name "unconnected-(U$2-PadA22{slash}DAC1)") (class "Default")
      (node (ref "U$2") (pin "A22/DAC1") (pinfunction "A22/DAC1_A22/DAC1") (pintype "bidirectional"))
    )
    (net (code "133") (name "unconnected-(U$2-PadPROG)") (class "Default")
      (node (ref "U$2") (pin "PROG") (pinfunction "PROG_PROG") (pintype "bidirectional"))
    )
    (net (code "134") (name "unconnected-(U$2-PadRESET)") (class "Default")
      (node (ref "U$2") (pin "RESET") (pinfunction "RESET_RESET") (pintype "bidirectional"))
    )
    (net (code "135") (name "unconnected-(U$2-PadU5V)") (class "Default")
      (node (ref "U$2") (pin "U5V") (pinfunction "U5V_U5V") (pintype "bidirectional"))
    )
    (net (code "136") (name "unconnected-(U$2-PadUD+)") (class "Default")
      (node (ref "U$2") (pin "UD+") (pinfunction "UD+_UD+") (pintype "bidirectional"))
    )
    (net (code "137") (name "unconnected-(U$2-PadUD-)") (class "Default")
      (node (ref "U$2") (pin "UD-") (pinfunction "UD-_UD-") (pintype "bidirectional"))
    )
    (net (code "138") (name "unconnected-(U$2-PadVBAT)") (class "Default")
      (node (ref "U$2") (pin "VBAT") (pinfunction "VBAT_VBAT") (pintype "bidirectional"))
    )
    (net (code "139") (name "unconnected-(U$2-PadVUSB)") (class "Default")
      (node (ref "U$2") (pin "VUSB") (pinfunction "VUSB_VUSB") (pintype "bidirectional"))
    )
  )
)
